# ADC.net
KiCad netlist of a schematic drawn in Altium Designer
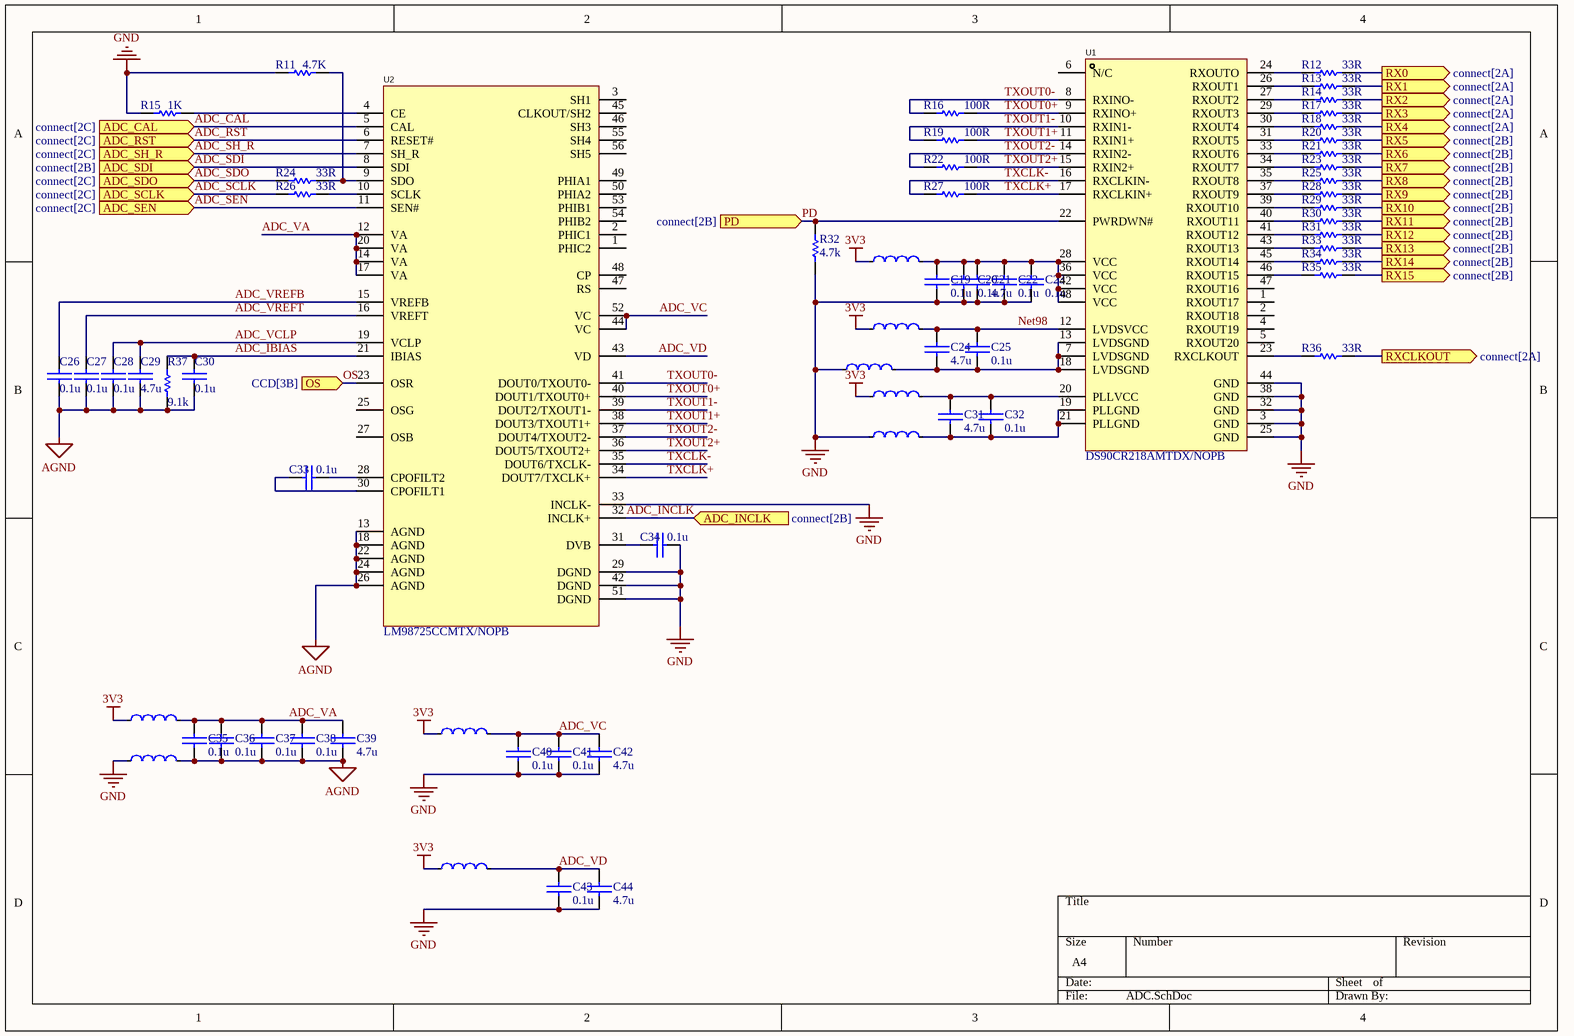
[diagram p0: ADC.SchDoc]

(export (version "E")
  (design (tool "Eeschema 10.0.6"))
  (components
    (comp (ref "C19")
      (value "0.1u")
      (footprint "0603C")
      (description "无极性电容")
      (libsource (lib "1.00-阻容感") (part "CAP"))
    )
    (comp (ref "C20")
      (value "0.1u")
      (footprint "0603C")
      (description "无极性电容")
      (libsource (lib "1.00-阻容感") (part "CAP"))
    )
    (comp (ref "C21")
      (value "4.7u")
      (footprint "0603C")
      (description "无极性电容")
      (libsource (lib "1.00-阻容感") (part "CAP"))
    )
    (comp (ref "C22")
      (value "0.1u")
      (footprint "0603C")
      (description "无极性电容")
      (libsource (lib "1.00-阻容感") (part "CAP"))
    )
    (comp (ref "C23")
      (value "0.1u")
      (footprint "0603C")
      (description "无极性电容")
      (libsource (lib "1.00-阻容感") (part "CAP"))
    )
    (comp (ref "C24")
      (value "4.7u")
      (footprint "0603C")
      (description "无极性电容")
      (libsource (lib "1.00-阻容感") (part "CAP"))
    )
    (comp (ref "C25")
      (value "0.1u")
      (footprint "0603C")
      (description "无极性电容")
      (libsource (lib "1.00-阻容感") (part "CAP"))
    )
    (comp (ref "C26")
      (value "0.1u")
      (footprint "0603C")
      (description "无极性电容")
      (libsource (lib "1.00-阻容感") (part "CAP"))
    )
    (comp (ref "C27")
      (value "0.1u")
      (footprint "0603C")
      (description "无极性电容")
      (libsource (lib "1.00-阻容感") (part "CAP"))
    )
    (comp (ref "C28")
      (value "0.1u")
      (footprint "0603C")
      (description "无极性电容")
      (libsource (lib "1.00-阻容感") (part "CAP"))
    )
    (comp (ref "C29")
      (value "4.7u")
      (footprint "0603C")
      (description "无极性电容")
      (libsource (lib "1.00-阻容感") (part "CAP"))
    )
    (comp (ref "C30")
      (value "0.1u")
      (footprint "0603C")
      (description "无极性电容")
      (libsource (lib "1.00-阻容感") (part "CAP"))
    )
    (comp (ref "C31")
      (value "4.7u")
      (footprint "0603C")
      (description "无极性电容")
      (libsource (lib "1.00-阻容感") (part "CAP"))
    )
    (comp (ref "C32")
      (value "0.1u")
      (footprint "0603C")
      (description "无极性电容")
      (libsource (lib "1.00-阻容感") (part "CAP"))
    )
    (comp (ref "C33")
      (value "0.1u")
      (footprint "0603C")
      (description "无极性电容")
      (libsource (lib "1.00-阻容感") (part "CAP"))
    )
    (comp (ref "C34")
      (value "0.1u")
      (footprint "0603C")
      (description "无极性电容")
      (libsource (lib "1.00-阻容感") (part "CAP"))
    )
    (comp (ref "C35")
      (value "0.1u")
      (footprint "0603C")
      (description "无极性电容")
      (libsource (lib "1.00-阻容感") (part "CAP"))
    )
    (comp (ref "C36")
      (value "0.1u")
      (footprint "0603C")
      (description "无极性电容")
      (libsource (lib "1.00-阻容感") (part "CAP"))
    )
    (comp (ref "C37")
      (value "0.1u")
      (footprint "0603C")
      (description "无极性电容")
      (libsource (lib "1.00-阻容感") (part "CAP"))
    )
    (comp (ref "C38")
      (value "0.1u")
      (footprint "0603C")
      (description "无极性电容")
      (libsource (lib "1.00-阻容感") (part "CAP"))
    )
    (comp (ref "C39")
      (value "4.7u")
      (footprint "0603C")
      (description "无极性电容")
      (libsource (lib "1.00-阻容感") (part "CAP"))
    )
    (comp (ref "C40")
      (value "0.1u")
      (footprint "0603C")
      (description "无极性电容")
      (libsource (lib "1.00-阻容感") (part "CAP"))
    )
    (comp (ref "C41")
      (value "0.1u")
      (footprint "0603C")
      (description "无极性电容")
      (libsource (lib "1.00-阻容感") (part "CAP"))
    )
    (comp (ref "C42")
      (value "4.7u")
      (footprint "0603C")
      (description "无极性电容")
      (libsource (lib "1.00-阻容感") (part "CAP"))
    )
    (comp (ref "C43")
      (value "0.1u")
      (footprint "0603C")
      (description "无极性电容")
      (libsource (lib "1.00-阻容感") (part "CAP"))
    )
    (comp (ref "C44")
      (value "4.7u")
      (footprint "0603C")
      (description "无极性电容")
      (libsource (lib "1.00-阻容感") (part "CAP"))
    )
    (comp (ref "L4")
      (value "GZ1608D601TF")
      (footprint "0603L")
      (description "铁氧体磁珠")
      (fields (field (name "MANUFACTURER") "Sunlord(顺络)") (field (name "TOLERANCE") "±25%"))
      (libsource (lib "1.00-阻容感") (part "FB"))
    )
    (comp (ref "L5")
      (value "GZ1608D601TF")
      (footprint "0603L")
      (description "铁氧体磁珠")
      (fields (field (name "MANUFACTURER") "Sunlord(顺络)") (field (name "TOLERANCE") "±25%"))
      (libsource (lib "1.00-阻容感") (part "FB"))
    )
    (comp (ref "L6")
      (value "GZ1608D601TF")
      (footprint "0603L")
      (description "铁氧体磁珠")
      (fields (field (name "MANUFACTURER") "Sunlord(顺络)") (field (name "TOLERANCE") "±25%"))
      (libsource (lib "1.00-阻容感") (part "FB"))
    )
    (comp (ref "L7")
      (value "GZ1608D601TF")
      (footprint "0603L")
      (description "铁氧体磁珠")
      (fields (field (name "MANUFACTURER") "Sunlord(顺络)") (field (name "TOLERANCE") "±25%"))
      (libsource (lib "1.00-阻容感") (part "FB"))
    )
    (comp (ref "L8")
      (value "GZ1608D601TF")
      (footprint "0603L")
      (description "铁氧体磁珠")
      (fields (field (name "MANUFACTURER") "Sunlord(顺络)") (field (name "TOLERANCE") "±25%"))
      (libsource (lib "1.00-阻容感") (part "FB"))
    )
    (comp (ref "L9")
      (value "GZ1608D601TF")
      (footprint "0603L")
      (description "铁氧体磁珠")
      (fields (field (name "MANUFACTURER") "Sunlord(顺络)") (field (name "TOLERANCE") "±25%"))
      (libsource (lib "1.00-阻容感") (part "FB"))
    )
    (comp (ref "L10")
      (value "GZ1608D601TF")
      (footprint "0603L")
      (description "铁氧体磁珠")
      (fields (field (name "MANUFACTURER") "Sunlord(顺络)") (field (name "TOLERANCE") "±25%"))
      (libsource (lib "1.00-阻容感") (part "FB"))
    )
    (comp (ref "L11")
      (value "GZ1608D601TF")
      (footprint "0603L")
      (description "铁氧体磁珠")
      (fields (field (name "MANUFACTURER") "Sunlord(顺络)") (field (name "TOLERANCE") "±25%"))
      (libsource (lib "1.00-阻容感") (part "FB"))
    )
    (comp (ref "L12")
      (value "GZ1608D601TF")
      (footprint "0603L")
      (description "铁氧体磁珠")
      (fields (field (name "MANUFACTURER") "Sunlord(顺络)") (field (name "TOLERANCE") "±25%"))
      (libsource (lib "1.00-阻容感") (part "FB"))
    )
    (comp (ref "R11")
      (value "4.7K")
      (footprint "0603R")
      (description "电阻")
      (libsource (lib "1.00-阻容感") (part "RES"))
    )
    (comp (ref "R12")
      (value "33R")
      (footprint "0603R")
      (description "电阻")
      (libsource (lib "1.00-阻容感") (part "RES"))
    )
    (comp (ref "R13")
      (value "33R")
      (footprint "0603R")
      (description "电阻")
      (libsource (lib "1.00-阻容感") (part "RES"))
    )
    (comp (ref "R14")
      (value "33R")
      (footprint "0603R")
      (description "电阻")
      (libsource (lib "1.00-阻容感") (part "RES"))
    )
    (comp (ref "R15")
      (value "1K")
      (footprint "0603R")
      (description "电阻")
      (libsource (lib "1.00-阻容感") (part "RES"))
    )
    (comp (ref "R16")
      (value "100R")
      (footprint "0603R")
      (description "电阻")
      (libsource (lib "1.00-阻容感") (part "RES"))
    )
    (comp (ref "R17")
      (value "33R")
      (footprint "0603R")
      (description "电阻")
      (libsource (lib "1.00-阻容感") (part "RES"))
    )
    (comp (ref "R18")
      (value "33R")
      (footprint "0603R")
      (description "电阻")
      (libsource (lib "1.00-阻容感") (part "RES"))
    )
    (comp (ref "R19")
      (value "100R")
      (footprint "0603R")
      (description "电阻")
      (libsource (lib "1.00-阻容感") (part "RES"))
    )
    (comp (ref "R20")
      (value "33R")
      (footprint "0603R")
      (description "电阻")
      (libsource (lib "1.00-阻容感") (part "RES"))
    )
    (comp (ref "R21")
      (value "33R")
      (footprint "0603R")
      (description "电阻")
      (libsource (lib "1.00-阻容感") (part "RES"))
    )
    (comp (ref "R22")
      (value "100R")
      (footprint "0603R")
      (description "电阻")
      (libsource (lib "1.00-阻容感") (part "RES"))
    )
    (comp (ref "R23")
      (value "33R")
      (footprint "0603R")
      (description "电阻")
      (libsource (lib "1.00-阻容感") (part "RES"))
    )
    (comp (ref "R24")
      (value "33R")
      (footprint "0603R")
      (description "电阻")
      (libsource (lib "1.00-阻容感") (part "RES"))
    )
    (comp (ref "R25")
      (value "33R")
      (footprint "0603R")
      (description "电阻")
      (libsource (lib "1.00-阻容感") (part "RES"))
    )
    (comp (ref "R26")
      (value "33R")
      (footprint "0603R")
      (description "电阻")
      (libsource (lib "1.00-阻容感") (part "RES"))
    )
    (comp (ref "R27")
      (value "100R")
      (footprint "0603R")
      (description "电阻")
      (libsource (lib "1.00-阻容感") (part "RES"))
    )
    (comp (ref "R28")
      (value "33R")
      (footprint "0603R")
      (description "电阻")
      (libsource (lib "1.00-阻容感") (part "RES"))
    )
    (comp (ref "R29")
      (value "33R")
      (footprint "0603R")
      (description "电阻")
      (libsource (lib "1.00-阻容感") (part "RES"))
    )
    (comp (ref "R30")
      (value "33R")
      (footprint "0603R")
      (description "电阻")
      (libsource (lib "1.00-阻容感") (part "RES"))
    )
    (comp (ref "R31")
      (value "33R")
      (footprint "0603R")
      (description "电阻")
      (libsource (lib "1.00-阻容感") (part "RES"))
    )
    (comp (ref "R32")
      (value "4.7k")
      (footprint "0603R")
      (description "电阻")
      (libsource (lib "1.00-阻容感") (part "RES"))
    )
    (comp (ref "R33")
      (value "33R")
      (footprint "0603R")
      (description "电阻")
      (libsource (lib "1.00-阻容感") (part "RES"))
    )
    (comp (ref "R34")
      (value "33R")
      (footprint "0603R")
      (description "电阻")
      (libsource (lib "1.00-阻容感") (part "RES"))
    )
    (comp (ref "R35")
      (value "33R")
      (footprint "0603R")
      (description "电阻")
      (libsource (lib "1.00-阻容感") (part "RES"))
    )
    (comp (ref "R36")
      (value "33R")
      (footprint "0603R")
      (description "电阻")
      (libsource (lib "1.00-阻容感") (part "RES"))
    )
    (comp (ref "R37")
      (value "9.1k")
      (footprint "0603R")
      (description "电阻")
      (libsource (lib "1.00-阻容感") (part "RES"))
    )
    (comp (ref "U1")
      (value "DS90CR218AMTDX/NOPB")
      (footprint "TSSOP-48")
      (description "解串芯片")
      (fields (field (name "MANUFACTURER") "TI(德州仪器)"))
      (libsource (lib "0.05-mylib") (part "DS90CR218AMTDX/NOPB"))
    )
    (comp (ref "U2")
      (value "LM98725CCMTX/NOPB")
      (footprint "TSSOP-56")
      (description "CCD专用ADC")
      (fields (field (name "MANUFACTURER") "TI(德州仪器)"))
      (libsource (lib "0.05-mylib") (part "LM98725CCMTX/NOPB"))
    )
  )
  (nets
    (net (code "1") (name "/ADC_CAL") (class "Default")
      (node (ref "U2") (pin "5") (pinfunction "CAL_5") (pintype "passive"))
    )
    (net (code "2") (name "/ADC_IBIAS") (class "Default")
      (node (ref "C30") (pin "1") (pinfunction "1_1") (pintype "passive"))
      (node (ref "R37") (pin "2") (pinfunction "2_2") (pintype "passive"))
      (node (ref "U2") (pin "21") (pinfunction "IBIAS_21") (pintype "passive"))
    )
    (net (code "3") (name "/ADC_INCLK") (class "Default")
      (node (ref "U2") (pin "32") (pinfunction "INCLK+_32") (pintype "passive"))
    )
    (net (code "4") (name "/ADC_RST") (class "Default")
      (node (ref "U2") (pin "6") (pinfunction "RESET#_6") (pintype "passive"))
    )
    (net (code "5") (name "/ADC_SCLK") (class "Default")
      (node (ref "R26") (pin "1") (pinfunction "1_1") (pintype "passive"))
    )
    (net (code "6") (name "/ADC_SDI") (class "Default")
      (node (ref "U2") (pin "8") (pinfunction "SDI_8") (pintype "passive"))
    )
    (net (code "7") (name "/ADC_SDO") (class "Default")
      (node (ref "R24") (pin "1") (pinfunction "1_1") (pintype "passive"))
    )
    (net (code "8") (name "/ADC_SEN") (class "Default")
      (node (ref "U2") (pin "11") (pinfunction "SEN#_11") (pintype "passive"))
    )
    (net (code "9") (name "/ADC_SH_R") (class "Default")
      (node (ref "U2") (pin "7") (pinfunction "SH_R_7") (pintype "passive"))
    )
    (net (code "10") (name "/ADC_VA") (class "Default")
      (node (ref "C35") (pin "2") (pinfunction "2_2") (pintype "passive"))
      (node (ref "C36") (pin "2") (pinfunction "2_2") (pintype "passive"))
      (node (ref "C37") (pin "2") (pinfunction "2_2") (pintype "passive"))
      (node (ref "C38") (pin "2") (pinfunction "2_2") (pintype "passive"))
      (node (ref "C39") (pin "2") (pinfunction "2_2") (pintype "passive"))
      (node (ref "L9") (pin "2") (pinfunction "2_2") (pintype "passive"))
      (node (ref "U2") (pin "12") (pinfunction "VA_12") (pintype "passive"))
      (node (ref "U2") (pin "14") (pinfunction "VA_14") (pintype "passive"))
      (node (ref "U2") (pin "17") (pinfunction "VA_17") (pintype "passive"))
      (node (ref "U2") (pin "20") (pinfunction "VA_20") (pintype "passive"))
    )
    (net (code "11") (name "/ADC_VC") (class "Default")
      (node (ref "C40") (pin "2") (pinfunction "2_2") (pintype "passive"))
      (node (ref "C41") (pin "2") (pinfunction "2_2") (pintype "passive"))
      (node (ref "C42") (pin "2") (pinfunction "2_2") (pintype "passive"))
      (node (ref "L10") (pin "2") (pinfunction "2_2") (pintype "passive"))
      (node (ref "U2") (pin "44") (pinfunction "VC_44") (pintype "passive"))
      (node (ref "U2") (pin "52") (pinfunction "VC_52") (pintype "passive"))
    )
    (net (code "12") (name "/ADC_VCLP") (class "Default")
      (node (ref "C28") (pin "1") (pinfunction "1_1") (pintype "passive"))
      (node (ref "C29") (pin "1") (pinfunction "1_1") (pintype "passive"))
      (node (ref "U2") (pin "19") (pinfunction "VCLP_19") (pintype "passive"))
    )
    (net (code "13") (name "/ADC_VD") (class "Default")
      (node (ref "C43") (pin "2") (pinfunction "2_2") (pintype "passive"))
      (node (ref "C44") (pin "2") (pinfunction "2_2") (pintype "passive"))
      (node (ref "L12") (pin "2") (pinfunction "2_2") (pintype "passive"))
      (node (ref "U2") (pin "43") (pinfunction "VD_43") (pintype "passive"))
    )
    (net (code "14") (name "/ADC_VREFB") (class "Default")
      (node (ref "C26") (pin "1") (pinfunction "1_1") (pintype "passive"))
      (node (ref "U2") (pin "15") (pinfunction "VREFB_15") (pintype "passive"))
    )
    (net (code "15") (name "/ADC_VREFT") (class "Default")
      (node (ref "C27") (pin "1") (pinfunction "1_1") (pintype "passive"))
      (node (ref "U2") (pin "16") (pinfunction "VREFT_16") (pintype "passive"))
    )
    (net (code "16") (name "/Net98") (class "Default")
      (node (ref "C24") (pin "2") (pinfunction "2_2") (pintype "passive"))
      (node (ref "C25") (pin "2") (pinfunction "2_2") (pintype "passive"))
      (node (ref "L5") (pin "2") (pinfunction "2_2") (pintype "passive"))
      (node (ref "U1") (pin "12") (pinfunction "LVDSVCC_12") (pintype "passive"))
    )
    (net (code "17") (name "/OS") (class "Default")
      (node (ref "U2") (pin "23") (pinfunction "OSR_23") (pintype "passive"))
    )
    (net (code "18") (name "/PD") (class "Default")
      (node (ref "R32") (pin "2") (pinfunction "2_2") (pintype "passive"))
      (node (ref "U1") (pin "22") (pinfunction "PWRDWN#_22") (pintype "passive"))
    )
    (net (code "19") (name "/RX0") (class "Default")
      (node (ref "R12") (pin "2") (pinfunction "2_2") (pintype "passive"))
    )
    (net (code "20") (name "/RX1") (class "Default")
      (node (ref "R13") (pin "2") (pinfunction "2_2") (pintype "passive"))
    )
    (net (code "21") (name "/RX2") (class "Default")
      (node (ref "R14") (pin "2") (pinfunction "2_2") (pintype "passive"))
    )
    (net (code "22") (name "/RX3") (class "Default")
      (node (ref "R17") (pin "2") (pinfunction "2_2") (pintype "passive"))
    )
    (net (code "23") (name "/RX4") (class "Default")
      (node (ref "R18") (pin "2") (pinfunction "2_2") (pintype "passive"))
    )
    (net (code "24") (name "/RX5") (class "Default")
      (node (ref "R20") (pin "2") (pinfunction "2_2") (pintype "passive"))
    )
    (net (code "25") (name "/RX6") (class "Default")
      (node (ref "R21") (pin "2") (pinfunction "2_2") (pintype "passive"))
    )
    (net (code "26") (name "/RX7") (class "Default")
      (node (ref "R23") (pin "2") (pinfunction "2_2") (pintype "passive"))
    )
    (net (code "27") (name "/RX8") (class "Default")
      (node (ref "R25") (pin "2") (pinfunction "2_2") (pintype "passive"))
    )
    (net (code "28") (name "/RX9") (class "Default")
      (node (ref "R28") (pin "2") (pinfunction "2_2") (pintype "passive"))
    )
    (net (code "29") (name "/RX10") (class "Default")
      (node (ref "R29") (pin "2") (pinfunction "2_2") (pintype "passive"))
    )
    (net (code "30") (name "/RX11") (class "Default")
      (node (ref "R30") (pin "2") (pinfunction "2_2") (pintype "passive"))
    )
    (net (code "31") (name "/RX12") (class "Default")
      (node (ref "R31") (pin "2") (pinfunction "2_2") (pintype "passive"))
    )
    (net (code "32") (name "/RX13") (class "Default")
      (node (ref "R33") (pin "2") (pinfunction "2_2") (pintype "passive"))
    )
    (net (code "33") (name "/RX14") (class "Default")
      (node (ref "R34") (pin "2") (pinfunction "2_2") (pintype "passive"))
    )
    (net (code "34") (name "/RX15") (class "Default")
      (node (ref "R35") (pin "2") (pinfunction "2_2") (pintype "passive"))
    )
    (net (code "35") (name "/RXCLKOUT") (class "Default")
      (node (ref "R36") (pin "2") (pinfunction "2_2") (pintype "passive"))
    )
    (net (code "36") (name "/TXCLK+") (class "Default")
      (node (ref "R27") (pin "2") (pinfunction "2_2") (pintype "passive"))
      (node (ref "U1") (pin "17") (pinfunction "RXCLKIN+_17") (pintype "passive"))
      (node (ref "U2") (pin "34") (pinfunction "DOUT7/TXCLK+_34") (pintype "passive"))
    )
    (net (code "37") (name "/TXCLK-") (class "Default")
      (node (ref "R27") (pin "1") (pinfunction "1_1") (pintype "passive"))
      (node (ref "U1") (pin "16") (pinfunction "RXCLKIN-_16") (pintype "passive"))
      (node (ref "U2") (pin "35") (pinfunction "DOUT6/TXCLK-_35") (pintype "passive"))
    )
    (net (code "38") (name "/TXOUT0+") (class "Default")
      (node (ref "R16") (pin "2") (pinfunction "2_2") (pintype "passive"))
      (node (ref "U1") (pin "9") (pinfunction "RXINO+_9") (pintype "passive"))
      (node (ref "U2") (pin "40") (pinfunction "DOUT1/TXOUT0+_40") (pintype "passive"))
    )
    (net (code "39") (name "/TXOUT0-") (class "Default")
      (node (ref "R16") (pin "1") (pinfunction "1_1") (pintype "passive"))
      (node (ref "U1") (pin "8") (pinfunction "RXINO-_8") (pintype "passive"))
      (node (ref "U2") (pin "41") (pinfunction "DOUT0/TXOUT0-_41") (pintype "passive"))
    )
    (net (code "40") (name "/TXOUT1+") (class "Default")
      (node (ref "R19") (pin "2") (pinfunction "2_2") (pintype "passive"))
      (node (ref "U1") (pin "11") (pinfunction "RXIN1+_11") (pintype "passive"))
      (node (ref "U2") (pin "38") (pinfunction "DOUT3/TXOUT1+_38") (pintype "passive"))
    )
    (net (code "41") (name "/TXOUT1-") (class "Default")
      (node (ref "R19") (pin "1") (pinfunction "1_1") (pintype "passive"))
      (node (ref "U1") (pin "10") (pinfunction "RXIN1-_10") (pintype "passive"))
      (node (ref "U2") (pin "39") (pinfunction "DOUT2/TXOUT1-_39") (pintype "passive"))
    )
    (net (code "42") (name "/TXOUT2+") (class "Default")
      (node (ref "R22") (pin "2") (pinfunction "2_2") (pintype "passive"))
      (node (ref "U1") (pin "15") (pinfunction "RXIN2+_15") (pintype "passive"))
      (node (ref "U2") (pin "36") (pinfunction "DOUT5/TXOUT2+_36") (pintype "passive"))
    )
    (net (code "43") (name "/TXOUT2-") (class "Default")
      (node (ref "R22") (pin "1") (pinfunction "1_1") (pintype "passive"))
      (node (ref "U1") (pin "14") (pinfunction "RXIN2-_14") (pintype "passive"))
      (node (ref "U2") (pin "37") (pinfunction "DOUT4/TXOUT2-_37") (pintype "passive"))
    )
    (net (code "44") (name "3V3") (class "Default")
      (node (ref "L10") (pin "1") (pinfunction "1_1") (pintype "passive"))
      (node (ref "L12") (pin "1") (pinfunction "1_1") (pintype "passive"))
      (node (ref "L4") (pin "1") (pinfunction "1_1") (pintype "passive"))
      (node (ref "L5") (pin "1") (pinfunction "1_1") (pintype "passive"))
      (node (ref "L7") (pin "1") (pinfunction "1_1") (pintype "passive"))
      (node (ref "L9") (pin "1") (pinfunction "1_1") (pintype "passive"))
    )
    (net (code "45") (name "AGND") (class "Default")
      (node (ref "C26") (pin "2") (pinfunction "2_2") (pintype "passive"))
      (node (ref "C27") (pin "2") (pinfunction "2_2") (pintype "passive"))
      (node (ref "C28") (pin "2") (pinfunction "2_2") (pintype "passive"))
      (node (ref "C29") (pin "2") (pinfunction "2_2") (pintype "passive"))
      (node (ref "C30") (pin "2") (pinfunction "2_2") (pintype "passive"))
      (node (ref "C35") (pin "1") (pinfunction "1_1") (pintype "passive"))
      (node (ref "C36") (pin "1") (pinfunction "1_1") (pintype "passive"))
      (node (ref "C37") (pin "1") (pinfunction "1_1") (pintype "passive"))
      (node (ref "C38") (pin "1") (pinfunction "1_1") (pintype "passive"))
      (node (ref "C39") (pin "1") (pinfunction "1_1") (pintype "passive"))
      (node (ref "L11") (pin "2") (pinfunction "2_2") (pintype "passive"))
      (node (ref "R37") (pin "1") (pinfunction "1_1") (pintype "passive"))
      (node (ref "U2") (pin "13") (pinfunction "AGND_13") (pintype "passive"))
      (node (ref "U2") (pin "18") (pinfunction "AGND_18") (pintype "passive"))
      (node (ref "U2") (pin "22") (pinfunction "AGND_22") (pintype "passive"))
      (node (ref "U2") (pin "24") (pinfunction "AGND_24") (pintype "passive"))
      (node (ref "U2") (pin "26") (pinfunction "AGND_26") (pintype "passive"))
    )
    (net (code "46") (name "GND") (class "Default")
      (node (ref "C19") (pin "1") (pinfunction "1_1") (pintype "passive"))
      (node (ref "C20") (pin "1") (pinfunction "1_1") (pintype "passive"))
      (node (ref "C21") (pin "1") (pinfunction "1_1") (pintype "passive"))
      (node (ref "C22") (pin "1") (pinfunction "1_1") (pintype "passive"))
      (node (ref "C23") (pin "1") (pinfunction "1_1") (pintype "passive"))
      (node (ref "C34") (pin "2") (pinfunction "2_2") (pintype "passive"))
      (node (ref "C40") (pin "1") (pinfunction "1_1") (pintype "passive"))
      (node (ref "C41") (pin "1") (pinfunction "1_1") (pintype "passive"))
      (node (ref "C42") (pin "1") (pinfunction "1_1") (pintype "passive"))
      (node (ref "C43") (pin "1") (pinfunction "1_1") (pintype "passive"))
      (node (ref "C44") (pin "1") (pinfunction "1_1") (pintype "passive"))
      (node (ref "L11") (pin "1") (pinfunction "1_1") (pintype "passive"))
      (node (ref "L6") (pin "1") (pinfunction "1_1") (pintype "passive"))
      (node (ref "L8") (pin "1") (pinfunction "1_1") (pintype "passive"))
      (node (ref "R11") (pin "1") (pinfunction "1_1") (pintype "passive"))
      (node (ref "R15") (pin "1") (pinfunction "1_1") (pintype "passive"))
      (node (ref "R32") (pin "1") (pinfunction "1_1") (pintype "passive"))
      (node (ref "U1") (pin "25") (pinfunction "GND_25") (pintype "passive"))
      (node (ref "U1") (pin "3") (pinfunction "GND_3") (pintype "passive"))
      (node (ref "U1") (pin "32") (pinfunction "GND_32") (pintype "passive"))
      (node (ref "U1") (pin "38") (pinfunction "GND_38") (pintype "passive"))
      (node (ref "U1") (pin "44") (pinfunction "GND_44") (pintype "passive"))
      (node (ref "U2") (pin "29") (pinfunction "DGND_29") (pintype "passive"))
      (node (ref "U2") (pin "33") (pinfunction "INCLK-_33") (pintype "passive"))
      (node (ref "U2") (pin "42") (pinfunction "DGND_42") (pintype "passive"))
      (node (ref "U2") (pin "51") (pinfunction "DGND_51") (pintype "passive"))
    )
    (net (code "47") (name "Net-(C19-Pad2)") (class "Default")
      (node (ref "C19") (pin "2") (pinfunction "2_2") (pintype "passive"))
      (node (ref "C20") (pin "2") (pinfunction "2_2") (pintype "passive"))
      (node (ref "C21") (pin "2") (pinfunction "2_2") (pintype "passive"))
      (node (ref "C22") (pin "2") (pinfunction "2_2") (pintype "passive"))
      (node (ref "C23") (pin "2") (pinfunction "2_2") (pintype "passive"))
      (node (ref "L4") (pin "2") (pinfunction "2_2") (pintype "passive"))
      (node (ref "U1") (pin "28") (pinfunction "VCC_28") (pintype "passive"))
      (node (ref "U1") (pin "36") (pinfunction "VCC_36") (pintype "passive"))
      (node (ref "U1") (pin "42") (pinfunction "VCC_42") (pintype "passive"))
      (node (ref "U1") (pin "48") (pinfunction "VCC_48") (pintype "passive"))
    )
    (net (code "48") (name "Net-(C24-Pad1)") (class "Default")
      (node (ref "C24") (pin "1") (pinfunction "1_1") (pintype "passive"))
      (node (ref "C25") (pin "1") (pinfunction "1_1") (pintype "passive"))
      (node (ref "L6") (pin "2") (pinfunction "2_2") (pintype "passive"))
      (node (ref "U1") (pin "13") (pinfunction "LVDSGND_13") (pintype "passive"))
      (node (ref "U1") (pin "18") (pinfunction "LVDSGND_18") (pintype "passive"))
      (node (ref "U1") (pin "7") (pinfunction "LVDSGND_7") (pintype "passive"))
    )
    (net (code "49") (name "Net-(C31-Pad1)") (class "Default")
      (node (ref "C31") (pin "1") (pinfunction "1_1") (pintype "passive"))
      (node (ref "C32") (pin "1") (pinfunction "1_1") (pintype "passive"))
      (node (ref "L8") (pin "2") (pinfunction "2_2") (pintype "passive"))
      (node (ref "U1") (pin "19") (pinfunction "PLLGND_19") (pintype "passive"))
      (node (ref "U1") (pin "21") (pinfunction "PLLGND_21") (pintype "passive"))
    )
    (net (code "50") (name "Net-(U1-PLLVCC)") (class "Default")
      (node (ref "C31") (pin "2") (pinfunction "2_2") (pintype "passive"))
      (node (ref "C32") (pin "2") (pinfunction "2_2") (pintype "passive"))
      (node (ref "L7") (pin "2") (pinfunction "2_2") (pintype "passive"))
      (node (ref "U1") (pin "20") (pinfunction "PLLVCC_20") (pintype "passive"))
    )
    (net (code "51") (name "Net-(U1-RXCLKOUT)") (class "Default")
      (node (ref "R36") (pin "1") (pinfunction "1_1") (pintype "passive"))
      (node (ref "U1") (pin "23") (pinfunction "RXCLKOUT_23") (pintype "passive"))
    )
    (net (code "52") (name "Net-(U1-RXOUT1)") (class "Default")
      (node (ref "R13") (pin "1") (pinfunction "1_1") (pintype "passive"))
      (node (ref "U1") (pin "26") (pinfunction "RXOUT1_26") (pintype "passive"))
    )
    (net (code "53") (name "Net-(U1-RXOUT2)") (class "Default")
      (node (ref "R14") (pin "1") (pinfunction "1_1") (pintype "passive"))
      (node (ref "U1") (pin "27") (pinfunction "RXOUT2_27") (pintype "passive"))
    )
    (net (code "54") (name "Net-(U1-RXOUT3)") (class "Default")
      (node (ref "R17") (pin "1") (pinfunction "1_1") (pintype "passive"))
      (node (ref "U1") (pin "29") (pinfunction "RXOUT3_29") (pintype "passive"))
    )
    (net (code "55") (name "Net-(U1-RXOUT4)") (class "Default")
      (node (ref "R18") (pin "1") (pinfunction "1_1") (pintype "passive"))
      (node (ref "U1") (pin "30") (pinfunction "RXOUT4_30") (pintype "passive"))
    )
    (net (code "56") (name "Net-(U1-RXOUT5)") (class "Default")
      (node (ref "R20") (pin "1") (pinfunction "1_1") (pintype "passive"))
      (node (ref "U1") (pin "31") (pinfunction "RXOUT5_31") (pintype "passive"))
    )
    (net (code "57") (name "Net-(U1-RXOUT6)") (class "Default")
      (node (ref "R21") (pin "1") (pinfunction "1_1") (pintype "passive"))
      (node (ref "U1") (pin "33") (pinfunction "RXOUT6_33") (pintype "passive"))
    )
    (net (code "58") (name "Net-(U1-RXOUT7)") (class "Default")
      (node (ref "R23") (pin "1") (pinfunction "1_1") (pintype "passive"))
      (node (ref "U1") (pin "34") (pinfunction "RXOUT7_34") (pintype "passive"))
    )
    (net (code "59") (name "Net-(U1-RXOUT8)") (class "Default")
      (node (ref "R25") (pin "1") (pinfunction "1_1") (pintype "passive"))
      (node (ref "U1") (pin "35") (pinfunction "RXOUT8_35") (pintype "passive"))
    )
    (net (code "60") (name "Net-(U1-RXOUT9)") (class "Default")
      (node (ref "R28") (pin "1") (pinfunction "1_1") (pintype "passive"))
      (node (ref "U1") (pin "37") (pinfunction "RXOUT9_37") (pintype "passive"))
    )
    (net (code "61") (name "Net-(U1-RXOUT10)") (class "Default")
      (node (ref "R29") (pin "1") (pinfunction "1_1") (pintype "passive"))
      (node (ref "U1") (pin "39") (pinfunction "RXOUT10_39") (pintype "passive"))
    )
    (net (code "62") (name "Net-(U1-RXOUT11)") (class "Default")
      (node (ref "R30") (pin "1") (pinfunction "1_1") (pintype "passive"))
      (node (ref "U1") (pin "40") (pinfunction "RXOUT11_40") (pintype "passive"))
    )
    (net (code "63") (name "Net-(U1-RXOUT12)") (class "Default")
      (node (ref "R31") (pin "1") (pinfunction "1_1") (pintype "passive"))
      (node (ref "U1") (pin "41") (pinfunction "RXOUT12_41") (pintype "passive"))
    )
    (net (code "64") (name "Net-(U1-RXOUT13)") (class "Default")
      (node (ref "R33") (pin "1") (pinfunction "1_1") (pintype "passive"))
      (node (ref "U1") (pin "43") (pinfunction "RXOUT13_43") (pintype "passive"))
    )
    (net (code "65") (name "Net-(U1-RXOUT14)") (class "Default")
      (node (ref "R34") (pin "1") (pinfunction "1_1") (pintype "passive"))
      (node (ref "U1") (pin "45") (pinfunction "RXOUT14_45") (pintype "passive"))
    )
    (net (code "66") (name "Net-(U1-RXOUT15)") (class "Default")
      (node (ref "R35") (pin "1") (pinfunction "1_1") (pintype "passive"))
      (node (ref "U1") (pin "46") (pinfunction "RXOUT15_46") (pintype "passive"))
    )
    (net (code "67") (name "Net-(U1-RXOUTO)") (class "Default")
      (node (ref "R12") (pin "1") (pinfunction "1_1") (pintype "passive"))
      (node (ref "U1") (pin "24") (pinfunction "RXOUTO_24") (pintype "passive"))
    )
    (net (code "68") (name "Net-(U2-CE)") (class "Default")
      (node (ref "R15") (pin "2") (pinfunction "2_2") (pintype "passive"))
      (node (ref "U2") (pin "4") (pinfunction "CE_4") (pintype "passive"))
    )
    (net (code "69") (name "Net-(U2-CPOFILT1)") (class "Default")
      (node (ref "C33") (pin "1") (pinfunction "1_1") (pintype "passive"))
      (node (ref "U2") (pin "30") (pinfunction "CPOFILT1_30") (pintype "passive"))
    )
    (net (code "70") (name "Net-(U2-CPOFILT2)") (class "Default")
      (node (ref "C33") (pin "2") (pinfunction "2_2") (pintype "passive"))
      (node (ref "U2") (pin "28") (pinfunction "CPOFILT2_28") (pintype "passive"))
    )
    (net (code "71") (name "Net-(U2-DVB)") (class "Default")
      (node (ref "C34") (pin "1") (pinfunction "1_1") (pintype "passive"))
      (node (ref "U2") (pin "31") (pinfunction "DVB_31") (pintype "passive"))
    )
    (net (code "72") (name "Net-(U2-SCLK)") (class "Default")
      (node (ref "R26") (pin "2") (pinfunction "2_2") (pintype "passive"))
      (node (ref "U2") (pin "10") (pinfunction "SCLK_10") (pintype "passive"))
    )
    (net (code "73") (name "Net-(U2-SDO)") (class "Default")
      (node (ref "R11") (pin "2") (pinfunction "2_2") (pintype "passive"))
      (node (ref "R24") (pin "2") (pinfunction "2_2") (pintype "passive"))
      (node (ref "U2") (pin "9") (pinfunction "SDO_9") (pintype "passive"))
    )
    (net (code "74") (name "unconnected-(U1-N{slash}C-Pad6)") (class "Default")
      (node (ref "U1") (pin "6") (pinfunction "N/C_6") (pintype "passive"))
    )
    (net (code "75") (name "unconnected-(U1-RXOUT16-Pad47)") (class "Default")
      (node (ref "U1") (pin "47") (pinfunction "RXOUT16_47") (pintype "passive"))
    )
    (net (code "76") (name "unconnected-(U1-RXOUT17-Pad1)") (class "Default")
      (node (ref "U1") (pin "1") (pinfunction "RXOUT17_1") (pintype "passive"))
    )
    (net (code "77") (name "unconnected-(U1-RXOUT18-Pad2)") (class "Default")
      (node (ref "U1") (pin "2") (pinfunction "RXOUT18_2") (pintype "passive"))
    )
    (net (code "78") (name "unconnected-(U1-RXOUT19-Pad4)") (class "Default")
      (node (ref "U1") (pin "4") (pinfunction "RXOUT19_4") (pintype "passive"))
    )
    (net (code "79") (name "unconnected-(U1-RXOUT20-Pad5)") (class "Default")
      (node (ref "U1") (pin "5") (pinfunction "RXOUT20_5") (pintype "passive"))
    )
    (net (code "80") (name "unconnected-(U2-CLKOUT{slash}SH2-Pad45)") (class "Default")
      (node (ref "U2") (pin "45") (pinfunction "CLKOUT/SH2_45") (pintype "passive"))
    )
    (net (code "81") (name "unconnected-(U2-CP-Pad48)") (class "Default")
      (node (ref "U2") (pin "48") (pinfunction "CP_48") (pintype "passive"))
    )
    (net (code "82") (name "unconnected-(U2-OSB-Pad27)") (class "Default")
      (node (ref "U2") (pin "27") (pinfunction "OSB_27") (pintype "passive"))
    )
    (net (code "83") (name "unconnected-(U2-OSG-Pad25)") (class "Default")
      (node (ref "U2") (pin "25") (pinfunction "OSG_25") (pintype "passive"))
    )
    (net (code "84") (name "unconnected-(U2-PHIA1-Pad49)") (class "Default")
      (node (ref "U2") (pin "49") (pinfunction "PHIA1_49") (pintype "passive"))
    )
    (net (code "85") (name "unconnected-(U2-PHIA2-Pad50)") (class "Default")
      (node (ref "U2") (pin "50") (pinfunction "PHIA2_50") (pintype "passive"))
    )
    (net (code "86") (name "unconnected-(U2-PHIB1-Pad53)") (class "Default")
      (node (ref "U2") (pin "53") (pinfunction "PHIB1_53") (pintype "passive"))
    )
    (net (code "87") (name "unconnected-(U2-PHIB2-Pad54)") (class "Default")
      (node (ref "U2") (pin "54") (pinfunction "PHIB2_54") (pintype "passive"))
    )
    (net (code "88") (name "unconnected-(U2-PHIC1-Pad2)") (class "Default")
      (node (ref "U2") (pin "2") (pinfunction "PHIC1_2") (pintype "passive"))
    )
    (net (code "89") (name "unconnected-(U2-PHIC2-Pad1)") (class "Default")
      (node (ref "U2") (pin "1") (pinfunction "PHIC2_1") (pintype "passive"))
    )
    (net (code "90") (name "unconnected-(U2-RS-Pad47)") (class "Default")
      (node (ref "U2") (pin "47") (pinfunction "RS_47") (pintype "passive"))
    )
    (net (code "91") (name "unconnected-(U2-SH1-Pad3)") (class "Default")
      (node (ref "U2") (pin "3") (pinfunction "SH1_3") (pintype "passive"))
    )
    (net (code "92") (name "unconnected-(U2-SH3-Pad46)") (class "Default")
      (node (ref "U2") (pin "46") (pinfunction "SH3_46") (pintype "passive"))
    )
    (net (code "93") (name "unconnected-(U2-SH4-Pad55)") (class "Default")
      (node (ref "U2") (pin "55") (pinfunction "SH4_55") (pintype "passive"))
    )
    (net (code "94") (name "unconnected-(U2-SH5-Pad56)") (class "Default")
      (node (ref "U2") (pin "56") (pinfunction "SH5_56") (pintype "passive"))
    )
  )
)
